# extBoard_sheet4_adc.net
KiCad netlist of a schematic drawn in Altium Designer
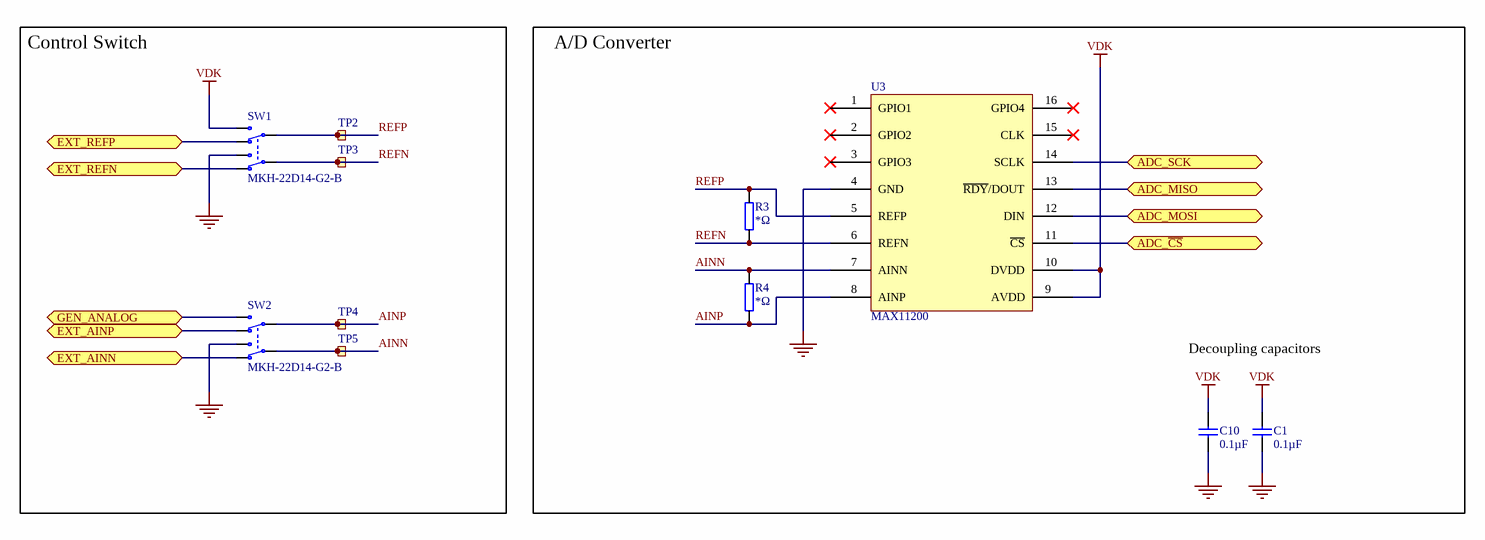
[diagram p0: extBoard_sheet4_adc.SchDoc]

(export (version "E")
  (design (tool "Eeschema 10.0.6"))
  (components
    (comp (ref "C1")
      (value "0.1µF")
      (footprint "CAPC2012X11L")
      (description "Capacitor, X5R, ±10%")
      (fields (field (name "PART NUMBER") "C0805-4µ7") (field (name "PUBLISHER") "Nordic Semiconductor"))
      (libsource (lib "pca10056") (part "CAP_0805"))
    )
    (comp (ref "C10")
      (value "0.1µF")
      (footprint "CAPC2012X11L")
      (description "Capacitor, X5R, ±10%")
      (fields (field (name "PART NUMBER") "C0805-4µ7") (field (name "PUBLISHER") "Nordic Semiconductor"))
      (libsource (lib "pca10056") (part "CAP_0805"))
    )
    (comp (ref "R3") (value "*Ω") (footprint "R0805") (libsource (lib "extBoardLib") (part "R0805")))
    (comp (ref "R4") (value "*Ω") (footprint "R0805") (libsource (lib "extBoardLib") (part "R0805")))
    (comp (ref "SW1")
      (value "MKH-22D14-G2-B")
      (footprint "MKH-22D14-G2-B")
      (description "Slide Switch DPDT")
      (fields (field (name "MANUFACTURER") "Dailywell") (field (name "PUBLISHER") "Nordic Semiconductor"))
      (libsource (lib "pca10056") (part "MKH-22D14-G2-B"))
    )
    (comp (ref "SW2")
      (value "MKH-22D14-G2-B")
      (footprint "MKH-22D14-G2-B")
      (description "Slide Switch DPDT")
      (fields (field (name "MANUFACTURER") "Dailywell") (field (name "PUBLISHER") "Nordic Semiconductor"))
      (libsource (lib "pca10056") (part "MKH-22D14-G2-B"))
    )
    (comp (ref "TP2")
      (value "TP")
      (footprint "TESTPAD-TH")
      (description "Testpoint, through hole")
      (fields (field (name "PART NUMBER") "Testpoint TH") (field (name "PUBLISHER") "Nordic Semiconductor"))
      (libsource (lib "pca10056") (part "Testpoint TH"))
    )
    (comp (ref "TP3")
      (value "TP")
      (footprint "TESTPAD-TH")
      (description "Testpoint, through hole")
      (fields (field (name "PART NUMBER") "Testpoint TH") (field (name "PUBLISHER") "Nordic Semiconductor"))
      (libsource (lib "pca10056") (part "Testpoint TH"))
    )
    (comp (ref "TP4")
      (value "TP")
      (footprint "TESTPAD-TH")
      (description "Testpoint, through hole")
      (fields (field (name "PART NUMBER") "Testpoint TH") (field (name "PUBLISHER") "Nordic Semiconductor"))
      (libsource (lib "pca10056") (part "Testpoint TH"))
    )
    (comp (ref "TP5")
      (value "TP")
      (footprint "TESTPAD-TH")
      (description "Testpoint, through hole")
      (fields (field (name "PART NUMBER") "Testpoint TH") (field (name "PUBLISHER") "Nordic Semiconductor"))
      (libsource (lib "pca10056") (part "Testpoint TH"))
    )
    (comp (ref "U3")
      (value "MAX11200")
      (footprint "QSOP16")
      (libsource (lib "extBoardLib") (part "MAX11200"))
    )
  )
  (nets
    (net (code "1") (name "/ADC_MISO") (class "Default")
      (node (ref "U3") (pin "13") (pinfunction "~{RDY}/DOUT_13") (pintype "passive"))
    )
    (net (code "2") (name "/ADC_MOSI") (class "Default")
      (node (ref "U3") (pin "12") (pinfunction "DIN_12") (pintype "passive"))
    )
    (net (code "3") (name "/ADC_SCK") (class "Default")
      (node (ref "U3") (pin "14") (pinfunction "SCLK_14") (pintype "passive"))
    )
    (net (code "4") (name "/ADC_~{CS}") (class "Default")
      (node (ref "U3") (pin "11") (pinfunction "~{CS}_11") (pintype "passive"))
    )
    (net (code "5") (name "/AINN") (class "Default")
      (node (ref "R4") (pin "2") (pinfunction "2_2") (pintype "passive"))
      (node (ref "SW2") (pin "2") (pinfunction "COM-1_2") (pintype "passive"))
      (node (ref "TP5") (pin "1") (pinfunction "1_1") (pintype "passive"))
      (node (ref "U3") (pin "7") (pinfunction "AINN_7") (pintype "passive"))
    )
    (net (code "6") (name "/AINP") (class "Default")
      (node (ref "R4") (pin "1") (pinfunction "1_1") (pintype "passive"))
      (node (ref "SW2") (pin "5") (pinfunction "COM-2_5") (pintype "passive"))
      (node (ref "TP4") (pin "1") (pinfunction "1_1") (pintype "passive"))
      (node (ref "U3") (pin "8") (pinfunction "AINP_8") (pintype "passive"))
    )
    (net (code "7") (name "/EXT_AINN") (class "Default")
      (node (ref "SW2") (pin "3") (pinfunction "N.C-1_3") (pintype "passive"))
    )
    (net (code "8") (name "/EXT_AINP") (class "Default")
      (node (ref "SW2") (pin "6") (pinfunction "N.C-2_6") (pintype "passive"))
    )
    (net (code "9") (name "/EXT_REFN") (class "Default")
      (node (ref "SW1") (pin "3") (pinfunction "N.C-1_3") (pintype "passive"))
    )
    (net (code "10") (name "/EXT_REFP") (class "Default")
      (node (ref "SW1") (pin "6") (pinfunction "N.C-2_6") (pintype "passive"))
    )
    (net (code "11") (name "/GEN_ANALOG") (class "Default")
      (node (ref "SW2") (pin "4") (pinfunction "N.O-2_4") (pintype "passive"))
    )
    (net (code "12") (name "/REFN") (class "Default")
      (node (ref "R3") (pin "1") (pinfunction "1_1") (pintype "passive"))
      (node (ref "SW1") (pin "2") (pinfunction "COM-1_2") (pintype "passive"))
      (node (ref "TP3") (pin "1") (pinfunction "1_1") (pintype "passive"))
      (node (ref "U3") (pin "6") (pinfunction "REFN_6") (pintype "passive"))
    )
    (net (code "13") (name "/REFP") (class "Default")
      (node (ref "R3") (pin "2") (pinfunction "2_2") (pintype "passive"))
      (node (ref "SW1") (pin "5") (pinfunction "COM-2_5") (pintype "passive"))
      (node (ref "TP2") (pin "1") (pinfunction "1_1") (pintype "passive"))
      (node (ref "U3") (pin "5") (pinfunction "REFP_5") (pintype "passive"))
    )
    (net (code "14") (name "GND") (class "Default")
      (node (ref "C1") (pin "1") (pinfunction "1_1") (pintype "passive"))
      (node (ref "C10") (pin "1") (pinfunction "1_1") (pintype "passive"))
      (node (ref "SW1") (pin "1") (pinfunction "N.O-1_1") (pintype "passive"))
      (node (ref "SW2") (pin "1") (pinfunction "N.O-1_1") (pintype "passive"))
      (node (ref "U3") (pin "4") (pinfunction "GND_4") (pintype "passive"))
    )
    (net (code "15") (name "VDK") (class "Default")
      (node (ref "C1") (pin "2") (pinfunction "2_2") (pintype "passive"))
      (node (ref "C10") (pin "2") (pinfunction "2_2") (pintype "passive"))
      (node (ref "SW1") (pin "4") (pinfunction "N.O-2_4") (pintype "passive"))
      (node (ref "U3") (pin "10") (pinfunction "DVDD_10") (pintype "passive"))
      (node (ref "U3") (pin "9") (pinfunction "AVDD_9") (pintype "passive"))
    )
    (net (code "16") (name "unconnected-(U3-CLK-Pad15)") (class "Default")
      (node (ref "U3") (pin "15") (pinfunction "CLK_15") (pintype "passive+no_connect"))
    )
    (net (code "17") (name "unconnected-(U3-GPIO1-Pad1)") (class "Default")
      (node (ref "U3") (pin "1") (pinfunction "GPIO1_1") (pintype "passive+no_connect"))
    )
    (net (code "18") (name "unconnected-(U3-GPIO2-Pad2)") (class "Default")
      (node (ref "U3") (pin "2") (pinfunction "GPIO2_2") (pintype "passive+no_connect"))
    )
    (net (code "19") (name "unconnected-(U3-GPIO3-Pad3)") (class "Default")
      (node (ref "U3") (pin "3") (pinfunction "GPIO3_3") (pintype "passive+no_connect"))
    )
    (net (code "20") (name "unconnected-(U3-GPIO4-Pad16)") (class "Default")
      (node (ref "U3") (pin "16") (pinfunction "GPIO4_16") (pintype "passive+no_connect"))
    )
  )
)
